# Guri_AVR_old.net
KiCad netlist of a schematic drawn in EAGLE
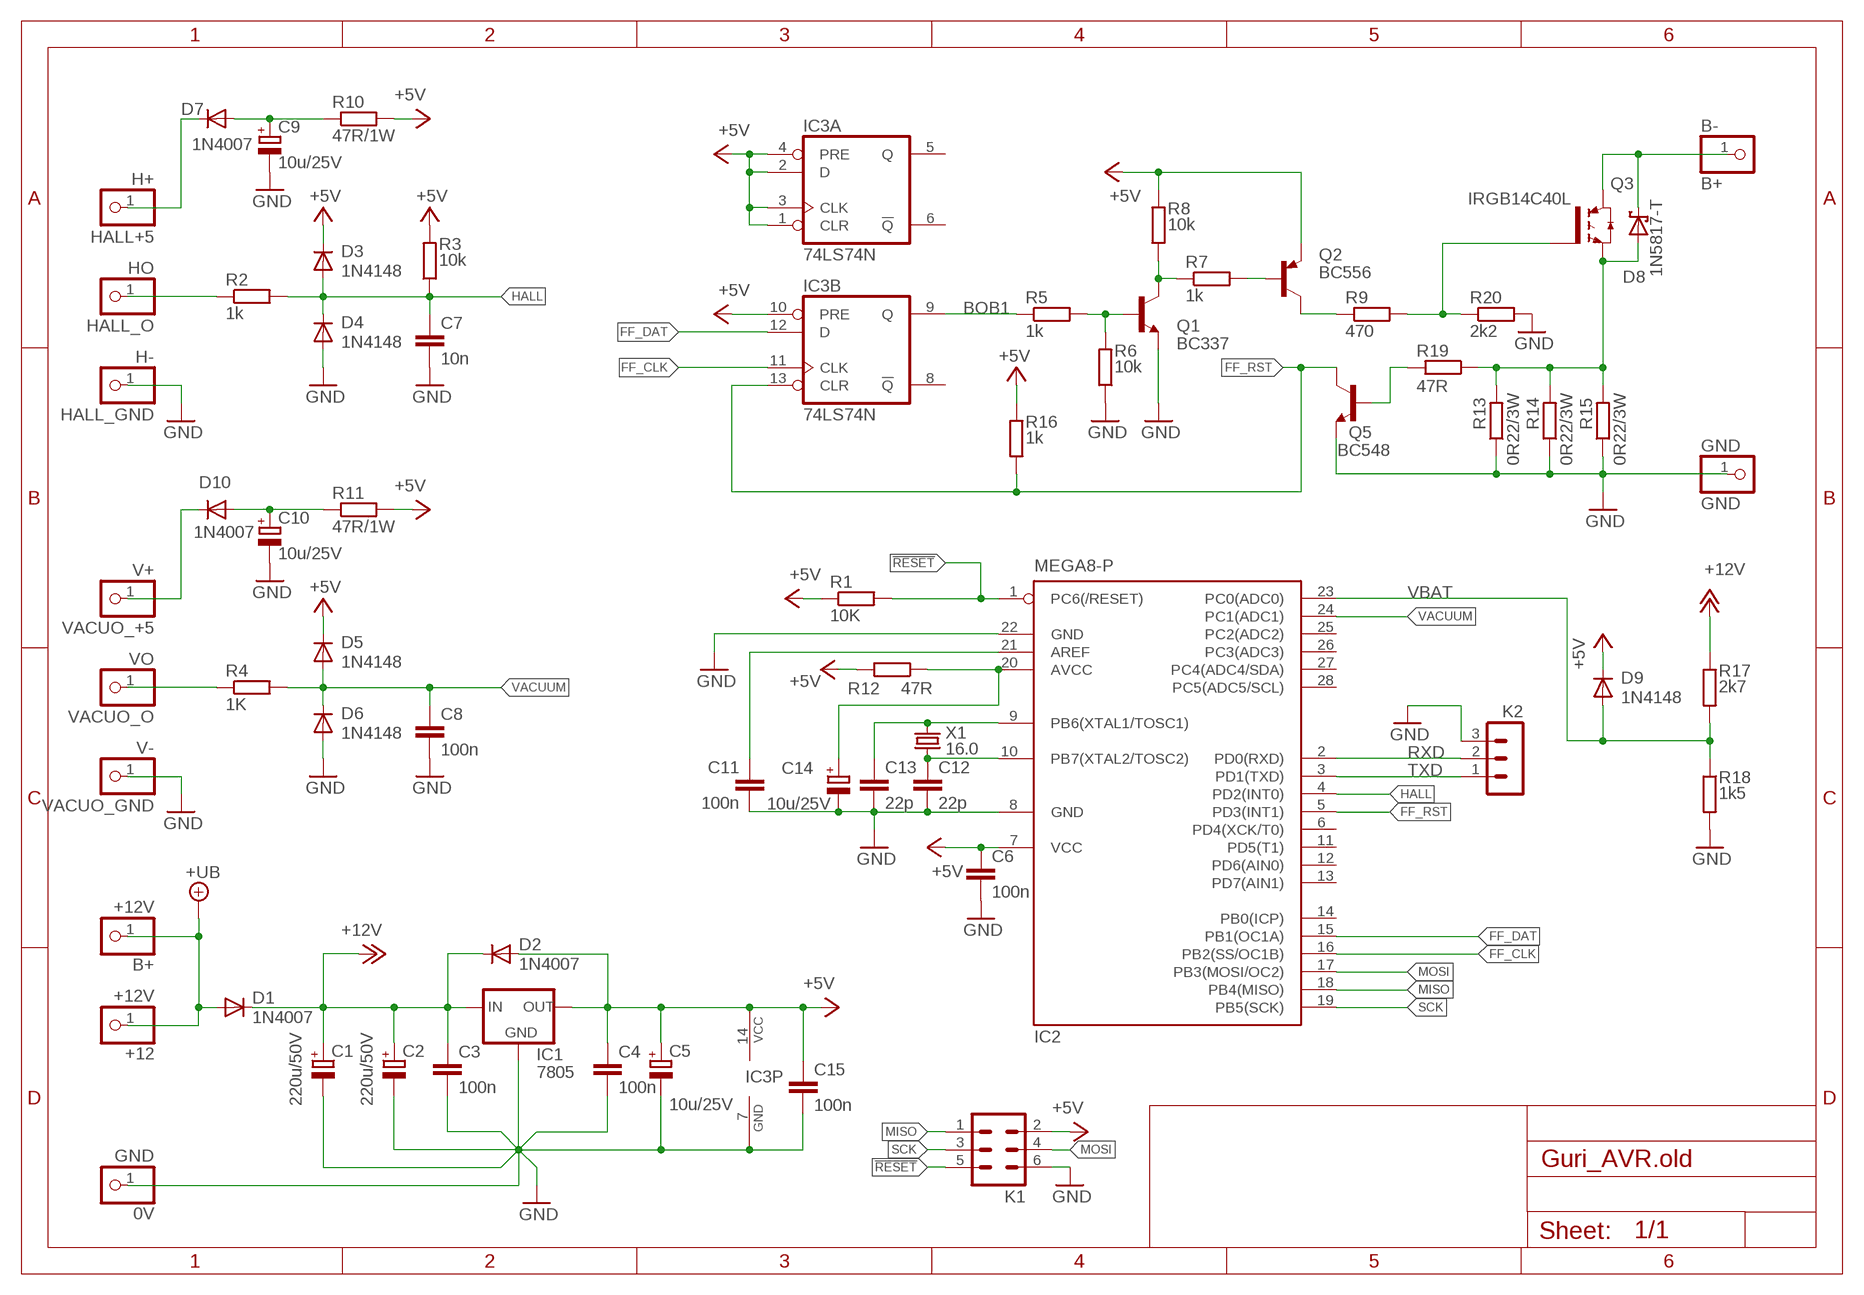
[diagram p0: schematic, sheet 1]

(export (version "E")
  (design (tool "Eeschema 10.0.6"))
  (components
    (comp (ref "+12")
      (value "+12V")
      (footprint "eagle-import:1X01")
      (libsource (lib "eagle-import") (part "PINHD-1X1"))
    )
    (comp (ref "0V")
      (value "GND")
      (footprint "eagle-import:1X01")
      (libsource (lib "eagle-import") (part "PINHD-1X1"))
    )
    (comp (ref "B+")
      (value "+12V")
      (footprint "eagle-import:1X01")
      (libsource (lib "eagle-import") (part "PINHD-1X1"))
    )
    (comp (ref "B-")
      (value "B+")
      (footprint "eagle-import:1X01")
      (libsource (lib "eagle-import") (part "PINHD-1X1"))
    )
    (comp (ref "C1")
      (value "220u/50V")
      (footprint "eagle-import:E5-10,5")
      (libsource (lib "eagle-import") (part "CPOL-EUE5-10.5"))
    )
    (comp (ref "C2")
      (value "220u/50V")
      (footprint "eagle-import:E5-10,5")
      (libsource (lib "eagle-import") (part "CPOL-EUE5-10.5"))
    )
    (comp (ref "C3")
      (value "100n")
      (footprint "eagle-import:C050-025X075")
      (libsource (lib "eagle-import") (part "C-EU050-025X075"))
    )
    (comp (ref "C4")
      (value "100n")
      (footprint "eagle-import:C050-025X075")
      (libsource (lib "eagle-import") (part "C-EU050-025X075"))
    )
    (comp (ref "C5")
      (value "10u/25V")
      (footprint "eagle-import:E2-5")
      (libsource (lib "eagle-import") (part "CPOL-EUE2-5"))
    )
    (comp (ref "C6")
      (value "100n")
      (footprint "eagle-import:C050-025X075")
      (libsource (lib "eagle-import") (part "C-EU050-025X075"))
    )
    (comp (ref "C7")
      (value "10n")
      (footprint "eagle-import:C050-025X075")
      (libsource (lib "eagle-import") (part "C-EU050-025X075"))
    )
    (comp (ref "C8")
      (value "100n")
      (footprint "eagle-import:C050-025X075")
      (libsource (lib "eagle-import") (part "C-EU050-025X075"))
    )
    (comp (ref "C9")
      (value "10u/25V")
      (footprint "eagle-import:E2-5")
      (libsource (lib "eagle-import") (part "CPOL-EUE2-5"))
    )
    (comp (ref "C10")
      (value "10u/25V")
      (footprint "eagle-import:E2-5")
      (libsource (lib "eagle-import") (part "CPOL-EUE2-5"))
    )
    (comp (ref "C11")
      (value "100n")
      (footprint "eagle-import:C050-025X075")
      (libsource (lib "eagle-import") (part "C-EU050-025X075"))
    )
    (comp (ref "C12")
      (value "22p")
      (footprint "eagle-import:C050-024X044")
      (libsource (lib "eagle-import") (part "C-EU050-024X044"))
    )
    (comp (ref "C13")
      (value "22p")
      (footprint "eagle-import:C050-024X044")
      (libsource (lib "eagle-import") (part "C-EU050-024X044"))
    )
    (comp (ref "C14")
      (value "10u/25V")
      (footprint "eagle-import:E2-5")
      (libsource (lib "eagle-import") (part "CPOL-EUE2-5"))
    )
    (comp (ref "C15")
      (value "100n")
      (footprint "eagle-import:C050-025X075")
      (libsource (lib "eagle-import") (part "C-EU050-025X075"))
    )
    (comp (ref "D1")
      (value "1N4007")
      (footprint "eagle-import:D-7.5")
      (libsource (lib "eagle-import") (part "DIODE-D-7.5"))
    )
    (comp (ref "D2")
      (value "1N4007")
      (footprint "eagle-import:D-7.5")
      (libsource (lib "eagle-import") (part "DIODE-D-7.5"))
    )
    (comp (ref "D3")
      (value "1N4148")
      (footprint "eagle-import:DO35-7")
      (libsource (lib "eagle-import") (part "1N4148DO35-7"))
    )
    (comp (ref "D4")
      (value "1N4148")
      (footprint "eagle-import:DO35-7")
      (libsource (lib "eagle-import") (part "1N4148DO35-7"))
    )
    (comp (ref "D5")
      (value "1N4148")
      (footprint "eagle-import:DO35-7")
      (libsource (lib "eagle-import") (part "1N4148DO35-7"))
    )
    (comp (ref "D6")
      (value "1N4148")
      (footprint "eagle-import:DO35-7")
      (libsource (lib "eagle-import") (part "1N4148DO35-7"))
    )
    (comp (ref "D7")
      (value "1N4007")
      (footprint "eagle-import:D-7.5")
      (libsource (lib "eagle-import") (part "DIODE-D-7.5"))
    )
    (comp (ref "D8")
      (value "1N5817-T")
      (footprint "eagle-import:DO41-7.6")
      (libsource (lib "eagle-import") (part "1N5817-T"))
    )
    (comp (ref "D9")
      (value "1N4148")
      (footprint "eagle-import:DO35-7")
      (libsource (lib "eagle-import") (part "1N4148DO35-7"))
    )
    (comp (ref "D10")
      (value "1N4007")
      (footprint "eagle-import:D-7.5")
      (libsource (lib "eagle-import") (part "DIODE-D-7.5"))
    )
    (comp (ref "GND")
      (value "GND")
      (footprint "eagle-import:1X01")
      (libsource (lib "eagle-import") (part "PINHD-1X1"))
    )
    (comp (ref "H+")
      (value "HALL+5")
      (footprint "eagle-import:1X01")
      (libsource (lib "eagle-import") (part "PINHD-1X1"))
    )
    (comp (ref "H-")
      (value "HALL_GND")
      (footprint "eagle-import:1X01")
      (libsource (lib "eagle-import") (part "PINHD-1X1"))
    )
    (comp (ref "HO")
      (value "HALL_O")
      (footprint "eagle-import:1X01")
      (libsource (lib "eagle-import") (part "PINHD-1X1"))
    )
    (comp (ref "IC1")
      (value "7805")
      (footprint "eagle-import:78XXS")
      (libsource (lib "eagle-import") (part "78XXS"))
    )
    (comp (ref "IC2")
      (value "MEGA8-P")
      (footprint "eagle-import:DIL28-3")
      (libsource (lib "eagle-import") (part "MEGA8-P"))
    )
    (comp (ref "IC3")
      (value "74LS74N")
      (footprint "eagle-import:DIL14")
      (libsource (lib "eagle-import") (part "7474NLS"))
    )
    (comp (ref "K1")
      (value "ML6")
      (footprint "eagle-import:ML6")
      (libsource (lib "eagle-import") (part "ML6"))
    )
    (comp (ref "K2")
      (value "MA03-1")
      (footprint "eagle-import:MA03-1")
      (libsource (lib "eagle-import") (part "MA03-1"))
    )
    (comp (ref "Q1")
      (value "BC337")
      (footprint "eagle-import:TO92-EBC")
      (libsource (lib "eagle-import") (part "BC338"))
    )
    (comp (ref "Q2")
      (value "BC556")
      (footprint "eagle-import:TO92-EBC")
      (libsource (lib "eagle-import") (part "BC556"))
    )
    (comp (ref "Q3")
      (value "IRGB14C40L")
      (footprint "eagle-import:TO262-V")
      (libsource (lib "eagle-import") (part "IRG4BC15UD--L"))
    )
    (comp (ref "Q5")
      (value "BC548")
      (footprint "eagle-import:TO92-EBC")
      (libsource (lib "eagle-import") (part "BC338"))
    )
    (comp (ref "R1")
      (value "10K")
      (footprint "eagle-import:0207_7L")
      (libsource (lib "eagle-import") (part "R-EU_0207/7L"))
    )
    (comp (ref "R2")
      (value "1k")
      (footprint "eagle-import:0207_7L")
      (libsource (lib "eagle-import") (part "R-EU_0207/7L"))
    )
    (comp (ref "R3")
      (value "10k")
      (footprint "eagle-import:0207_7L")
      (libsource (lib "eagle-import") (part "R-EU_0207/7L"))
    )
    (comp (ref "R4")
      (value "1K")
      (footprint "eagle-import:0207_7L")
      (libsource (lib "eagle-import") (part "R-EU_0207/7L"))
    )
    (comp (ref "R5")
      (value "1k")
      (footprint "eagle-import:0207_7L")
      (libsource (lib "eagle-import") (part "R-EU_0207/7L"))
    )
    (comp (ref "R6")
      (value "10k")
      (footprint "eagle-import:0207_7L")
      (libsource (lib "eagle-import") (part "R-EU_0207/7L"))
    )
    (comp (ref "R7")
      (value "1k")
      (footprint "eagle-import:0207_7L")
      (libsource (lib "eagle-import") (part "R-EU_0207/7L"))
    )
    (comp (ref "R8")
      (value "10k")
      (footprint "eagle-import:0207_7L")
      (libsource (lib "eagle-import") (part "R-EU_0207/7L"))
    )
    (comp (ref "R9")
      (value "470")
      (footprint "eagle-import:0207_7L")
      (libsource (lib "eagle-import") (part "R-EU_0207/7L"))
    )
    (comp (ref "R10")
      (value "47R/1W")
      (footprint "eagle-import:0207_7L")
      (libsource (lib "eagle-import") (part "R-EU_0207/7L"))
    )
    (comp (ref "R11")
      (value "47R/1W")
      (footprint "eagle-import:0207_7L")
      (libsource (lib "eagle-import") (part "R-EU_0207/7L"))
    )
    (comp (ref "R12")
      (value "47R")
      (footprint "eagle-import:0207_7L")
      (libsource (lib "eagle-import") (part "R-EU_0207/7L"))
    )
    (comp (ref "R13")
      (value "0R22/3W")
      (footprint "eagle-import:0309_10")
      (libsource (lib "eagle-import") (part "R-EU_0309/10"))
    )
    (comp (ref "R14")
      (value "0R22/3W")
      (footprint "eagle-import:0309_10")
      (libsource (lib "eagle-import") (part "R-EU_0309/10"))
    )
    (comp (ref "R15")
      (value "0R22/3W")
      (footprint "eagle-import:0309_10")
      (libsource (lib "eagle-import") (part "R-EU_0309/10"))
    )
    (comp (ref "R16")
      (value "1k")
      (footprint "eagle-import:0207_7L")
      (libsource (lib "eagle-import") (part "R-EU_0207/7L"))
    )
    (comp (ref "R17")
      (value "2k7")
      (footprint "eagle-import:0207_7L")
      (libsource (lib "eagle-import") (part "R-EU_0207/7L"))
    )
    (comp (ref "R18")
      (value "1k5")
      (footprint "eagle-import:0207_7L")
      (libsource (lib "eagle-import") (part "R-EU_0207/7L"))
    )
    (comp (ref "R19")
      (value "47R")
      (footprint "eagle-import:0207_7L")
      (libsource (lib "eagle-import") (part "R-EU_0207/7L"))
    )
    (comp (ref "R20")
      (value "2k2")
      (footprint "eagle-import:0207_7L")
      (libsource (lib "eagle-import") (part "R-EU_0207/7L"))
    )
    (comp (ref "V+")
      (value "VACUO_+5")
      (footprint "eagle-import:1X01")
      (libsource (lib "eagle-import") (part "PINHD-1X1"))
    )
    (comp (ref "V-")
      (value "VACUO_GND")
      (footprint "eagle-import:1X01")
      (libsource (lib "eagle-import") (part "PINHD-1X1"))
    )
    (comp (ref "VO")
      (value "VACUO_O")
      (footprint "eagle-import:1X01")
      (libsource (lib "eagle-import") (part "PINHD-1X1"))
    )
    (comp (ref "X1")
      (value "16.0")
      (footprint "eagle-import:HC49_S")
      (libsource (lib "eagle-import") (part "CRYSTALHC49S"))
    )
  )
  (nets
    (net (code "1") (name "+5V") (class "Default")
      (node (ref "C15") (pin "1") (pinfunction "1_1") (pintype "passive"))
      (node (ref "C4") (pin "1") (pinfunction "1_1") (pintype "passive"))
      (node (ref "C5") (pin "+") (pinfunction "+_+") (pintype "passive"))
      (node (ref "C6") (pin "1") (pinfunction "1_1") (pintype "passive"))
      (node (ref "D2") (pin "A") (pinfunction "A_A") (pintype "passive"))
      (node (ref "D3") (pin "C") (pinfunction "C_C") (pintype "passive"))
      (node (ref "D5") (pin "C") (pinfunction "C_C") (pintype "passive"))
      (node (ref "D9") (pin "C") (pinfunction "C_C") (pintype "passive"))
      (node (ref "IC1") (pin "OUT") (pinfunction "OUT_OUT") (pintype "passive"))
      (node (ref "IC2") (pin "7") (pinfunction "VCC_7") (pintype "power_in"))
      (node (ref "IC3") (pin "1") (pinfunction "CLR_1") (pintype "input"))
      (node (ref "IC3") (pin "10") (pinfunction "PRE_10") (pintype "input"))
      (node (ref "IC3") (pin "14") (pinfunction "VCC_14") (pintype "power_in"))
      (node (ref "IC3") (pin "2") (pinfunction "D_2") (pintype "input"))
      (node (ref "IC3") (pin "3") (pinfunction "CLK_3") (pintype "input"))
      (node (ref "IC3") (pin "4") (pinfunction "PRE_4") (pintype "input"))
      (node (ref "K1") (pin "2") (pinfunction "2_2") (pintype "passive"))
      (node (ref "Q2") (pin "E") (pinfunction "E_E") (pintype "passive"))
      (node (ref "R1") (pin "3") (pinfunction "1_3") (pintype "passive"))
      (node (ref "R10") (pin "4") (pinfunction "2_4") (pintype "passive"))
      (node (ref "R11") (pin "4") (pinfunction "2_4") (pintype "passive"))
      (node (ref "R12") (pin "4") (pinfunction "2_4") (pintype "passive"))
      (node (ref "R16") (pin "4") (pinfunction "2_4") (pintype "passive"))
      (node (ref "R3") (pin "4") (pinfunction "2_4") (pintype "passive"))
      (node (ref "R8") (pin "4") (pinfunction "2_4") (pintype "passive"))
    )
    (net (code "2") (name "+12V") (class "Default")
      (node (ref "C1") (pin "+") (pinfunction "+_+") (pintype "passive"))
      (node (ref "C2") (pin "+") (pinfunction "+_+") (pintype "passive"))
      (node (ref "C3") (pin "1") (pinfunction "1_1") (pintype "passive"))
      (node (ref "D1") (pin "C") (pinfunction "C_C") (pintype "passive"))
      (node (ref "D2") (pin "C") (pinfunction "C_C") (pintype "passive"))
      (node (ref "IC1") (pin "IN") (pinfunction "IN_IN") (pintype "input"))
      (node (ref "R17") (pin "3") (pinfunction "1_3") (pintype "passive"))
    )
    (net (code "3") (name "+UB") (class "Default")
      (node (ref "+12") (pin "1") (pinfunction "1_1") (pintype "passive"))
      (node (ref "B+") (pin "1") (pinfunction "1_1") (pintype "passive"))
      (node (ref "D1") (pin "A") (pinfunction "A_A") (pintype "passive"))
    )
    (net (code "4") (name "/BOB1") (class "Default")
      (node (ref "IC3") (pin "9") (pinfunction "Q_9") (pintype "output"))
      (node (ref "R5") (pin "3") (pinfunction "1_3") (pintype "passive"))
    )
    (net (code "5") (name "/RXD") (class "Default")
      (node (ref "IC2") (pin "2") (pinfunction "PD0(RXD)_2") (pintype "bidirectional"))
      (node (ref "K2") (pin "2") (pinfunction "2_2") (pintype "passive"))
    )
    (net (code "6") (name "/TXD") (class "Default")
      (node (ref "IC2") (pin "3") (pinfunction "PD1(TXD)_3") (pintype "bidirectional"))
      (node (ref "K2") (pin "1") (pinfunction "1_1") (pintype "passive"))
    )
    (net (code "7") (name "/VBAT") (class "Default")
      (node (ref "D9") (pin "A") (pinfunction "A_A") (pintype "passive"))
      (node (ref "IC2") (pin "23") (pinfunction "PC0(ADC0)_23") (pintype "bidirectional"))
      (node (ref "R17") (pin "4") (pinfunction "2_4") (pintype "passive"))
      (node (ref "R18") (pin "3") (pinfunction "1_3") (pintype "passive"))
    )
    (net (code "8") (name "/~{RESET}") (class "Default")
      (node (ref "IC2") (pin "1") (pinfunction "PC6(/RESET)_1") (pintype "bidirectional"))
      (node (ref "K1") (pin "5") (pinfunction "5_5") (pintype "passive"))
      (node (ref "R1") (pin "4") (pinfunction "2_4") (pintype "passive"))
    )
    (net (code "9") (name "FF_CLK") (class "Default")
      (node (ref "IC2") (pin "16") (pinfunction "PB2(SS/OC1B)_16") (pintype "bidirectional"))
      (node (ref "IC3") (pin "11") (pinfunction "CLK_11") (pintype "input"))
    )
    (net (code "10") (name "FF_DAT") (class "Default")
      (node (ref "IC2") (pin "15") (pinfunction "PB1(OC1A)_15") (pintype "bidirectional"))
      (node (ref "IC3") (pin "12") (pinfunction "D_12") (pintype "input"))
    )
    (net (code "11") (name "FF_RST") (class "Default")
      (node (ref "IC2") (pin "5") (pinfunction "PD3(INT1)_5") (pintype "bidirectional"))
      (node (ref "IC3") (pin "13") (pinfunction "CLR_13") (pintype "input"))
      (node (ref "Q5") (pin "C") (pinfunction "C_C") (pintype "passive"))
      (node (ref "R16") (pin "3") (pinfunction "1_3") (pintype "passive"))
    )
    (net (code "12") (name "GND") (class "Default")
      (node (ref "0V") (pin "1") (pinfunction "1_1") (pintype "passive"))
      (node (ref "C1") (pin "-") (pinfunction "-_-") (pintype "passive"))
      (node (ref "C10") (pin "-") (pinfunction "-_-") (pintype "passive"))
      (node (ref "C11") (pin "2") (pinfunction "2_2") (pintype "passive"))
      (node (ref "C12") (pin "2") (pinfunction "2_2") (pintype "passive"))
      (node (ref "C13") (pin "2") (pinfunction "2_2") (pintype "passive"))
      (node (ref "C14") (pin "-") (pinfunction "-_-") (pintype "passive"))
      (node (ref "C15") (pin "2") (pinfunction "2_2") (pintype "passive"))
      (node (ref "C2") (pin "-") (pinfunction "-_-") (pintype "passive"))
      (node (ref "C3") (pin "2") (pinfunction "2_2") (pintype "passive"))
      (node (ref "C4") (pin "2") (pinfunction "2_2") (pintype "passive"))
      (node (ref "C5") (pin "-") (pinfunction "-_-") (pintype "passive"))
      (node (ref "C6") (pin "2") (pinfunction "2_2") (pintype "passive"))
      (node (ref "C7") (pin "2") (pinfunction "2_2") (pintype "passive"))
      (node (ref "C8") (pin "2") (pinfunction "2_2") (pintype "passive"))
      (node (ref "C9") (pin "-") (pinfunction "-_-") (pintype "passive"))
      (node (ref "D4") (pin "A") (pinfunction "A_A") (pintype "passive"))
      (node (ref "D6") (pin "A") (pinfunction "A_A") (pintype "passive"))
      (node (ref "GND") (pin "1") (pinfunction "1_1") (pintype "passive"))
      (node (ref "H-") (pin "1") (pinfunction "1_1") (pintype "passive"))
      (node (ref "IC1") (pin "GND") (pinfunction "GND_GND") (pintype "input"))
      (node (ref "IC2") (pin "22") (pinfunction "GND_22") (pintype "power_in"))
      (node (ref "IC2") (pin "8") (pinfunction "GND_8") (pintype "power_in"))
      (node (ref "IC3") (pin "7") (pinfunction "GND_7") (pintype "power_in"))
      (node (ref "K1") (pin "6") (pinfunction "6_6") (pintype "passive"))
      (node (ref "K2") (pin "3") (pinfunction "3_3") (pintype "passive"))
      (node (ref "Q1") (pin "E") (pinfunction "E_E") (pintype "passive"))
      (node (ref "Q5") (pin "E") (pinfunction "E_E") (pintype "passive"))
      (node (ref "R13") (pin "1") (pinfunction "1_1") (pintype "passive"))
      (node (ref "R14") (pin "1") (pinfunction "1_1") (pintype "passive"))
      (node (ref "R15") (pin "1") (pinfunction "1_1") (pintype "passive"))
      (node (ref "R18") (pin "4") (pinfunction "2_4") (pintype "passive"))
      (node (ref "R20") (pin "4") (pinfunction "2_4") (pintype "passive"))
      (node (ref "R6") (pin "3") (pinfunction "1_3") (pintype "passive"))
      (node (ref "V-") (pin "1") (pinfunction "1_1") (pintype "passive"))
    )
    (net (code "13") (name "HALL") (class "Default")
      (node (ref "C7") (pin "1") (pinfunction "1_1") (pintype "passive"))
      (node (ref "D3") (pin "A") (pinfunction "A_A") (pintype "passive"))
      (node (ref "D4") (pin "C") (pinfunction "C_C") (pintype "passive"))
      (node (ref "IC2") (pin "4") (pinfunction "PD2(INT0)_4") (pintype "bidirectional"))
      (node (ref "R2") (pin "4") (pinfunction "2_4") (pintype "passive"))
      (node (ref "R3") (pin "3") (pinfunction "1_3") (pintype "passive"))
    )
    (net (code "14") (name "MISO") (class "Default")
      (node (ref "IC2") (pin "18") (pinfunction "PB4(MISO)_18") (pintype "bidirectional"))
      (node (ref "K1") (pin "1") (pinfunction "1_1") (pintype "passive"))
    )
    (net (code "15") (name "MOSI") (class "Default")
      (node (ref "IC2") (pin "17") (pinfunction "PB3(MOSI/OC2)_17") (pintype "bidirectional"))
      (node (ref "K1") (pin "4") (pinfunction "4_4") (pintype "passive"))
    )
    (net (code "16") (name "Net-(D7-PadC)") (class "Default")
      (node (ref "D7") (pin "C") (pinfunction "C_C") (pintype "passive"))
      (node (ref "H+") (pin "1") (pinfunction "1_1") (pintype "passive"))
    )
    (net (code "17") (name "Net-(D10-PadC)") (class "Default")
      (node (ref "D10") (pin "C") (pinfunction "C_C") (pintype "passive"))
      (node (ref "V+") (pin "1") (pinfunction "1_1") (pintype "passive"))
    )
    (net (code "18") (name "Net-(IC2-AREF)") (class "Default")
      (node (ref "C11") (pin "1") (pinfunction "1_1") (pintype "passive"))
      (node (ref "IC2") (pin "21") (pinfunction "AREF_21") (pintype "passive"))
    )
    (net (code "19") (name "Net-(IC2-AVCC)") (class "Default")
      (node (ref "C14") (pin "+") (pinfunction "+_+") (pintype "passive"))
      (node (ref "IC2") (pin "20") (pinfunction "AVCC_20") (pintype "power_in"))
      (node (ref "R12") (pin "3") (pinfunction "1_3") (pintype "passive"))
    )
    (net (code "20") (name "Net-(IC2-PB6(XTAL1{slash}TOSC1))") (class "Default")
      (node (ref "C13") (pin "1") (pinfunction "1_1") (pintype "passive"))
      (node (ref "IC2") (pin "9") (pinfunction "PB6(XTAL1/TOSC1)_9") (pintype "bidirectional"))
      (node (ref "X1") (pin "2") (pinfunction "2_2") (pintype "passive"))
    )
    (net (code "21") (name "Net-(IC2-PB7(XTAL2{slash}TOSC2))") (class "Default")
      (node (ref "C12") (pin "1") (pinfunction "1_1") (pintype "passive"))
      (node (ref "IC2") (pin "10") (pinfunction "PB7(XTAL2/TOSC2)_10") (pintype "bidirectional"))
      (node (ref "X1") (pin "1") (pinfunction "1_1") (pintype "passive"))
    )
    (net (code "22") (name "Net-(Q3-C)") (class "Default")
      (node (ref "B-") (pin "1") (pinfunction "1_1") (pintype "passive"))
      (node (ref "D8") (pin "C") (pinfunction "C_C") (pintype "passive"))
      (node (ref "Q3") (pin "2") (pinfunction "C_2") (pintype "passive"))
    )
    (net (code "23") (name "Net-(Q3-E)") (class "Default")
      (node (ref "D8") (pin "A") (pinfunction "A_A") (pintype "passive"))
      (node (ref "Q3") (pin "3") (pinfunction "E_3") (pintype "passive"))
      (node (ref "R13") (pin "2") (pinfunction "2_2") (pintype "passive"))
      (node (ref "R14") (pin "2") (pinfunction "2_2") (pintype "passive"))
      (node (ref "R15") (pin "2") (pinfunction "2_2") (pintype "passive"))
      (node (ref "R19") (pin "3") (pinfunction "1_3") (pintype "passive"))
    )
    (net (code "24") (name "Net-(Q3-G)") (class "Default")
      (node (ref "Q3") (pin "1") (pinfunction "G_1") (pintype "passive"))
      (node (ref "R20") (pin "3") (pinfunction "1_3") (pintype "passive"))
      (node (ref "R9") (pin "4") (pinfunction "2_4") (pintype "passive"))
    )
    (net (code "25") (name "Net-(R2-1)") (class "Default")
      (node (ref "HO") (pin "1") (pinfunction "1_1") (pintype "passive"))
      (node (ref "R2") (pin "3") (pinfunction "1_3") (pintype "passive"))
    )
    (net (code "26") (name "Net-(R4-1)") (class "Default")
      (node (ref "R4") (pin "3") (pinfunction "1_3") (pintype "passive"))
      (node (ref "VO") (pin "1") (pinfunction "1_1") (pintype "passive"))
    )
    (net (code "27") (name "Net-(R5-2)") (class "Default")
      (node (ref "Q1") (pin "B") (pinfunction "B_B") (pintype "passive"))
      (node (ref "R5") (pin "4") (pinfunction "2_4") (pintype "passive"))
      (node (ref "R6") (pin "4") (pinfunction "2_4") (pintype "passive"))
    )
    (net (code "28") (name "Net-(R7-1)") (class "Default")
      (node (ref "Q1") (pin "C") (pinfunction "C_C") (pintype "passive"))
      (node (ref "R7") (pin "3") (pinfunction "1_3") (pintype "passive"))
      (node (ref "R8") (pin "3") (pinfunction "1_3") (pintype "passive"))
    )
    (net (code "29") (name "Net-(R7-2)") (class "Default")
      (node (ref "Q2") (pin "B") (pinfunction "B_B") (pintype "passive"))
      (node (ref "R7") (pin "4") (pinfunction "2_4") (pintype "passive"))
    )
    (net (code "30") (name "Net-(R9-1)") (class "Default")
      (node (ref "Q2") (pin "C") (pinfunction "C_C") (pintype "passive"))
      (node (ref "R9") (pin "3") (pinfunction "1_3") (pintype "passive"))
    )
    (net (code "31") (name "Net-(R10-1)") (class "Default")
      (node (ref "C9") (pin "+") (pinfunction "+_+") (pintype "passive"))
      (node (ref "D7") (pin "A") (pinfunction "A_A") (pintype "passive"))
      (node (ref "R10") (pin "3") (pinfunction "1_3") (pintype "passive"))
    )
    (net (code "32") (name "Net-(R11-1)") (class "Default")
      (node (ref "C10") (pin "+") (pinfunction "+_+") (pintype "passive"))
      (node (ref "D10") (pin "A") (pinfunction "A_A") (pintype "passive"))
      (node (ref "R11") (pin "3") (pinfunction "1_3") (pintype "passive"))
    )
    (net (code "33") (name "Net-(R19-2)") (class "Default")
      (node (ref "Q5") (pin "B") (pinfunction "B_B") (pintype "passive"))
      (node (ref "R19") (pin "4") (pinfunction "2_4") (pintype "passive"))
    )
    (net (code "34") (name "SCK") (class "Default")
      (node (ref "IC2") (pin "19") (pinfunction "PB5(SCK)_19") (pintype "bidirectional"))
      (node (ref "K1") (pin "3") (pinfunction "3_3") (pintype "passive"))
    )
    (net (code "35") (name "VACUUM") (class "Default")
      (node (ref "C8") (pin "1") (pinfunction "1_1") (pintype "passive"))
      (node (ref "D5") (pin "A") (pinfunction "A_A") (pintype "passive"))
      (node (ref "D6") (pin "C") (pinfunction "C_C") (pintype "passive"))
      (node (ref "IC2") (pin "24") (pinfunction "PC1(ADC1)_24") (pintype "bidirectional"))
      (node (ref "R4") (pin "4") (pinfunction "2_4") (pintype "passive"))
    )
    (net (code "36") (name "unconnected-(IC2-PB0(ICP)-Pad14)") (class "Default")
      (node (ref "IC2") (pin "14") (pinfunction "PB0(ICP)_14") (pintype "bidirectional"))
    )
    (net (code "37") (name "unconnected-(IC2-PC2(ADC2)-Pad25)") (class "Default")
      (node (ref "IC2") (pin "25") (pinfunction "PC2(ADC2)_25") (pintype "bidirectional"))
    )
    (net (code "38") (name "unconnected-(IC2-PC3(ADC3)-Pad26)") (class "Default")
      (node (ref "IC2") (pin "26") (pinfunction "PC3(ADC3)_26") (pintype "bidirectional"))
    )
    (net (code "39") (name "unconnected-(IC2-PC4(ADC4{slash}SDA)-Pad27)") (class "Default")
      (node (ref "IC2") (pin "27") (pinfunction "PC4(ADC4/SDA)_27") (pintype "bidirectional"))
    )
    (net (code "40") (name "unconnected-(IC2-PC5(ADC5{slash}SCL)-Pad28)") (class "Default")
      (node (ref "IC2") (pin "28") (pinfunction "PC5(ADC5/SCL)_28") (pintype "bidirectional"))
    )
    (net (code "41") (name "unconnected-(IC2-PD4(XCK{slash}T0)-Pad6)") (class "Default")
      (node (ref "IC2") (pin "6") (pinfunction "PD4(XCK/T0)_6") (pintype "bidirectional"))
    )
    (net (code "42") (name "unconnected-(IC2-PD5(T1)-Pad11)") (class "Default")
      (node (ref "IC2") (pin "11") (pinfunction "PD5(T1)_11") (pintype "bidirectional"))
    )
    (net (code "43") (name "unconnected-(IC2-PD6(AIN0)-Pad12)") (class "Default")
      (node (ref "IC2") (pin "12") (pinfunction "PD6(AIN0)_12") (pintype "bidirectional"))
    )
    (net (code "44") (name "unconnected-(IC2-PD7(AIN1)-Pad13)") (class "Default")
      (node (ref "IC2") (pin "13") (pinfunction "PD7(AIN1)_13") (pintype "bidirectional"))
    )
    (net (code "45") (name "unconnected-(IC3A-Q-Pad5)") (class "Default")
      (node (ref "IC3") (pin "5") (pinfunction "Q_5") (pintype "output"))
    )
    (net (code "46") (name "unconnected-(IC3A-~{Q}-Pad6)") (class "Default")
      (node (ref "IC3") (pin "6") (pinfunction "~{Q}_6") (pintype "output"))
    )
    (net (code "47") (name "unconnected-(IC3B-~{Q}-Pad8)") (class "Default")
      (node (ref "IC3") (pin "8") (pinfunction "~{Q}_8") (pintype "output"))
    )
  )
)
